# FMC_connector.net
KiCad netlist of a schematic drawn in Altium Designer
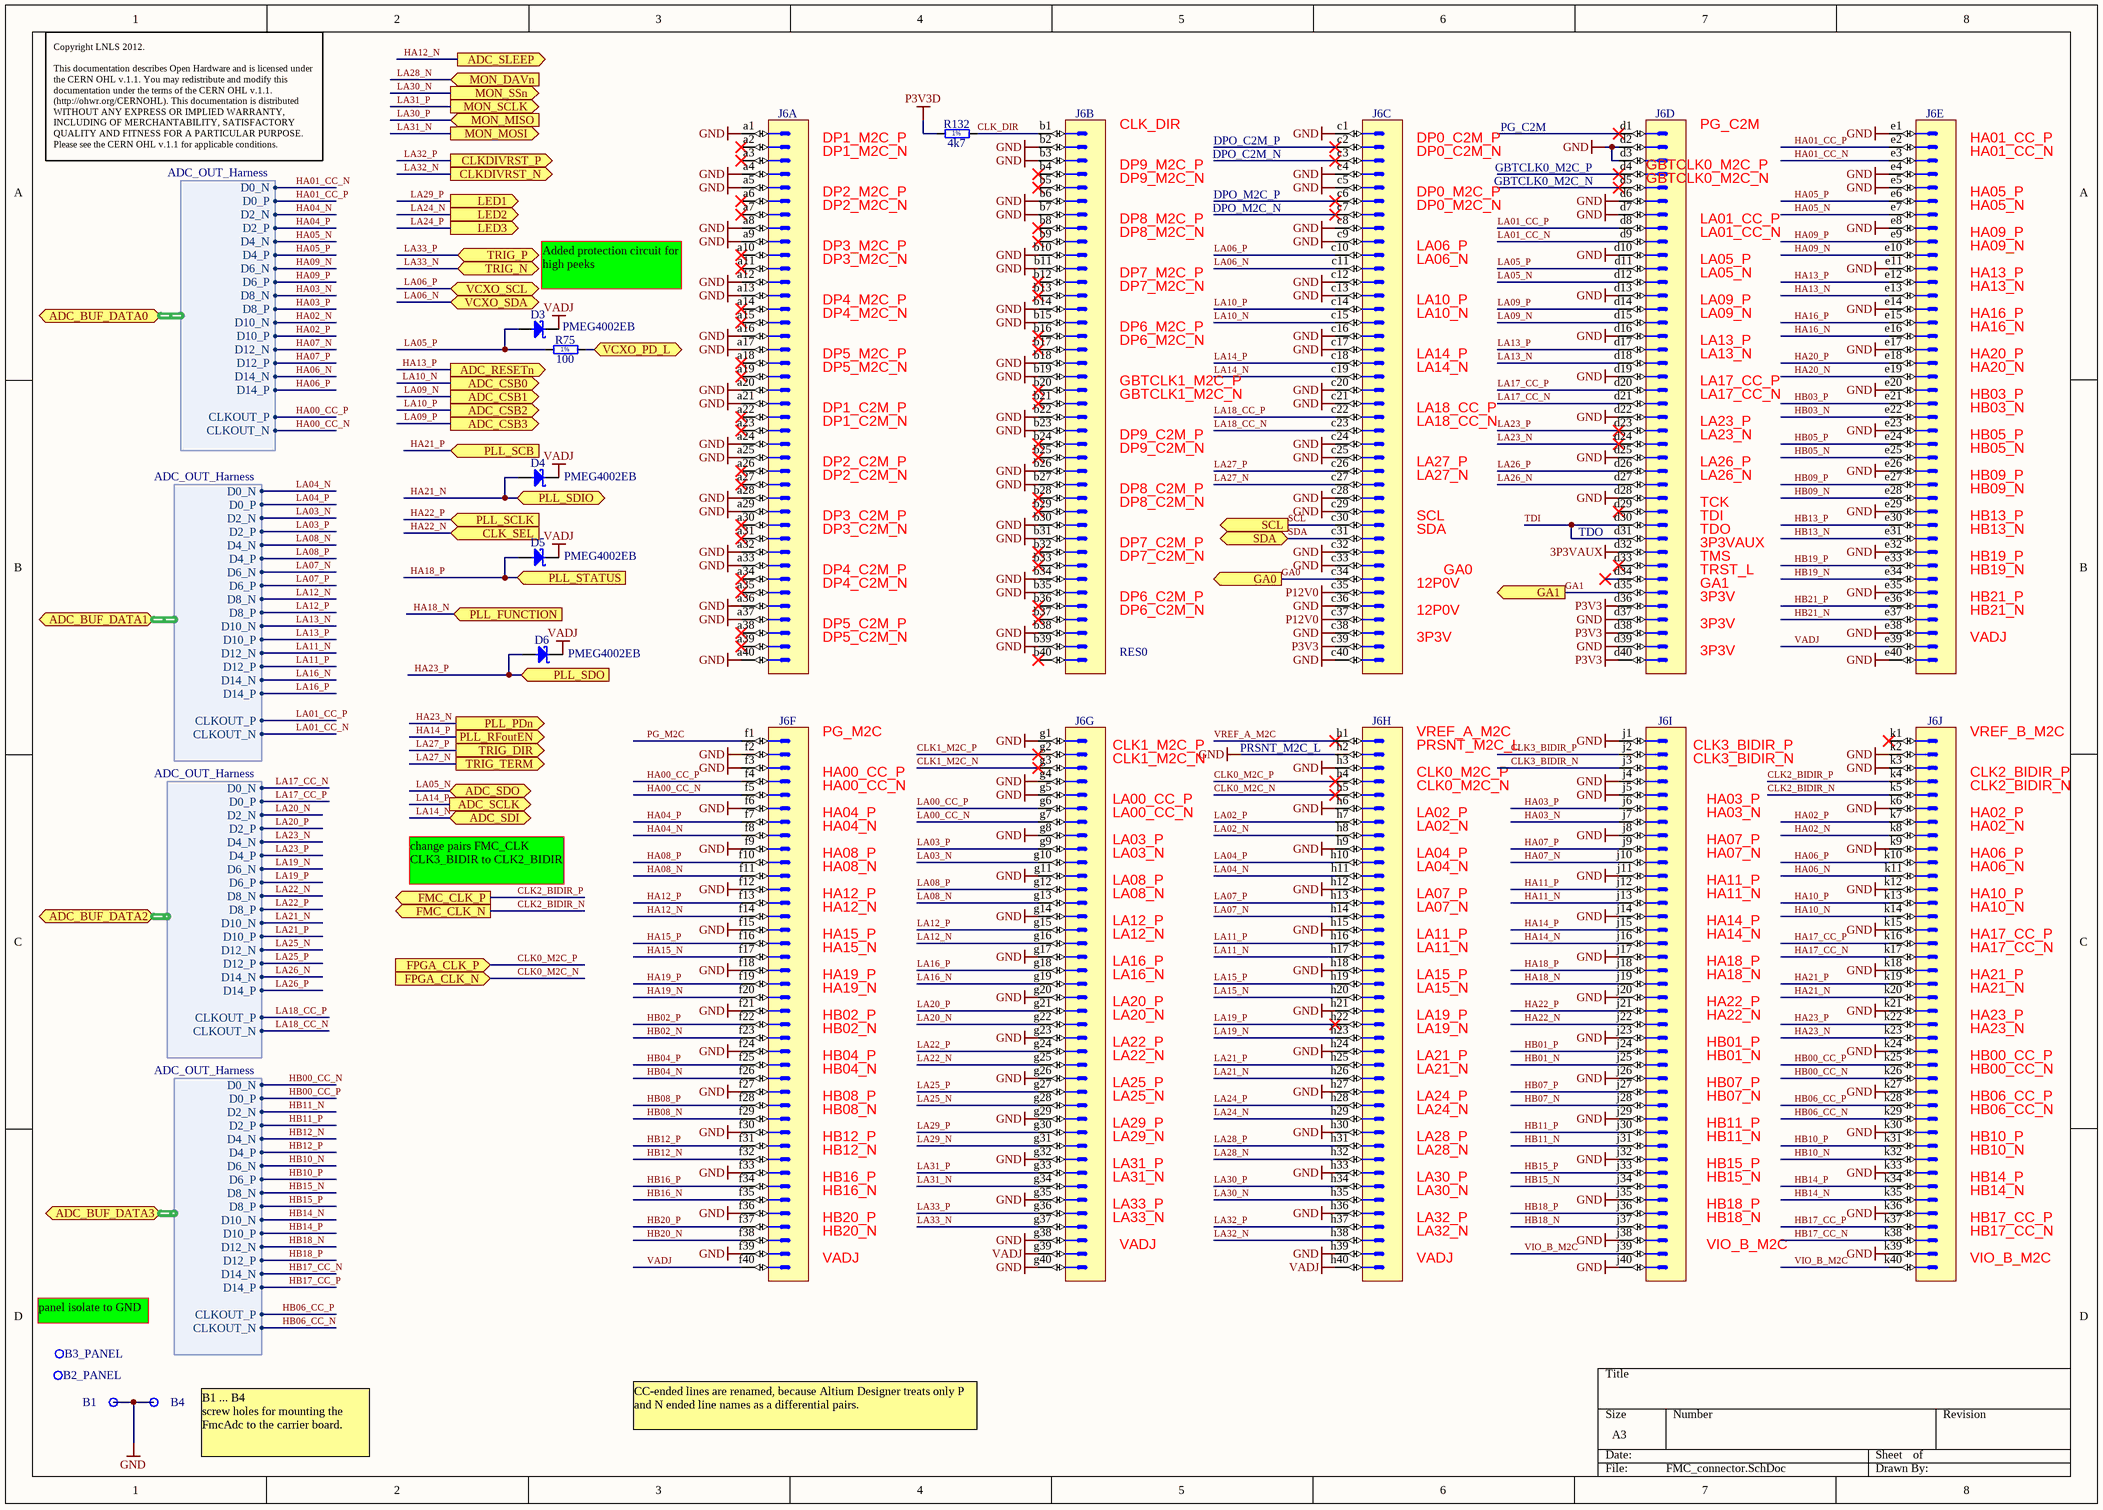
[diagram p0: FMC_connector.SchDoc]

(export (version "E")
  (design (tool "Eeschema 10.0.6"))
  (components
    (comp (ref "B1")
      (value "Plated Hole")
      (footprint "MTG270_500_M")
      (description "Single Terminal Socket")
      (fields (field (name "PART NUMBER") "PLATED_HOLE2.7_PAD5.0_M") (field (name "AUTHOR") "LNLS DIG FCS"))
      (libsource (lib "Eletro-mechanical") (part "Single Terminal Socket"))
    )
    (comp (ref "B2_PANEL")
      (value "Plated Hole")
      (footprint "MTG270_500_M")
      (description "Single Terminal Socket")
      (fields (field (name "PART NUMBER") "PLATED_HOLE2.7_PAD5.0_M") (field (name "AUTHOR") "LNLS DIG FCS"))
      (libsource (lib "Eletro-mechanical") (part "Single Terminal Socket"))
    )
    (comp (ref "B3_PANEL")
      (value "Plated Hole")
      (footprint "MTG270_500_M")
      (description "Single Terminal Socket")
      (fields (field (name "PART NUMBER") "PLATED_HOLE2.7_PAD5.0_M") (field (name "AUTHOR") "LNLS DIG FCS"))
      (libsource (lib "Eletro-mechanical") (part "Single Terminal Socket"))
    )
    (comp (ref "B4")
      (value "Plated Hole")
      (footprint "MTG270_500_M")
      (description "Single Terminal Socket")
      (fields (field (name "PART NUMBER") "PLATED_HOLE2.7_PAD5.0_M") (field (name "AUTHOR") "LNLS DIG FCS"))
      (libsource (lib "Eletro-mechanical") (part "Single Terminal Socket"))
    )
    (comp (ref "D3")
      (value "PMEG4002EB")
      (footprint "SODFL1608X65N")
      (description "Schottky Diode")
      (fields
        (field (name "VOLTAGE") "40V")
        (field (name "POWER") "200mA")
        (field (name "AUTHOR") "CERN DEM JMW")
      )
      (libsource (lib "ICs And Semiconductors") (part "Diode Schottky"))
    )
    (comp (ref "D4")
      (value "PMEG4002EB")
      (footprint "SODFL1608X65N")
      (description "Schottky Diode")
      (fields
        (field (name "VOLTAGE") "40V")
        (field (name "POWER") "200mA")
        (field (name "AUTHOR") "CERN DEM JMW")
      )
      (libsource (lib "ICs And Semiconductors") (part "Diode Schottky"))
    )
    (comp (ref "D5")
      (value "PMEG4002EB")
      (footprint "SODFL1608X65N")
      (description "Schottky Diode")
      (fields
        (field (name "VOLTAGE") "40V")
        (field (name "POWER") "200mA")
        (field (name "AUTHOR") "CERN DEM JMW")
      )
      (libsource (lib "ICs And Semiconductors") (part "Diode Schottky"))
    )
    (comp (ref "D6")
      (value "PMEG4002EB")
      (footprint "SODFL1608X65N")
      (description "Schottky Diode")
      (fields
        (field (name "VOLTAGE") "40V")
        (field (name "POWER") "200mA")
        (field (name "AUTHOR") "CERN DEM JMW")
      )
      (libsource (lib "ICs And Semiconductors") (part "Diode Schottky"))
    )
    (comp (ref "J6")
      (value "~")
      (footprint "SAMTEC_ASP-134488-01")
      (description "Connector VITA 57, 400 Male contacts in 10 row abcdefghj")
      (fields
        (field (name "PART NUMBER") "SAMTEC_ASP-134488-01")
        (field (name "MANUFACTURER") "SAMTEC")
        (field (name "AUTHOR") "CERN DEM JLC")
      )
      (libsource (lib "Connectors") (part "Connector VITA 57 400 Male (abcdefghjk)"))
    )
    (comp (ref "R75")
      (value "100")
      (footprint "RESC1005X40N")
      (description "Resistor - 1%")
      (fields
        (field (name "PART NUMBER") "R0402_100R_1%_0.0625W_100PPM")
        (field (name "POWER") "0.0625W")
        (field (name "AUTHOR") "CERN DEM JLC")
      )
      (libsource (lib "Resistors") (part "Resistor - 1%"))
    )
    (comp (ref "R132")
      (value "4k7")
      (footprint "RESC1005X40N")
      (description "Resistor - 1%")
      (fields
        (field (name "PART NUMBER") "R0402_4K7_1%_0.0625W_100PPM")
        (field (name "POWER") "0.0625W")
        (field (name "AUTHOR") "CERN DEM JLC")
      )
      (libsource (lib "Resistors") (part "Resistor - 1%"))
    )
  )
  (nets
    (net (code "2") (name "/CLK0_M2C_N") (class "Default")
      (node (ref "J6") (pin "h5") (pinfunction "h5_h5") (pintype "bidirectional+no_connect"))
    )
    (net (code "3") (name "/CLK0_M2C_P") (class "Default")
      (node (ref "J6") (pin "h4") (pinfunction "h4_h4") (pintype "bidirectional+no_connect"))
    )
    (net (code "4") (name "/CLK1_M2C_N") (class "Default")
      (node (ref "J6") (pin "g3") (pinfunction "g3_g3") (pintype "bidirectional+no_connect"))
    )
    (net (code "5") (name "/CLK1_M2C_P") (class "Default")
      (node (ref "J6") (pin "g2") (pinfunction "g2_g2") (pintype "bidirectional+no_connect"))
    )
    (net (code "6") (name "/CLK2_BIDIR_N") (class "Default")
      (node (ref "J6") (pin "k5") (pinfunction "k5_k5") (pintype "bidirectional"))
    )
    (net (code "7") (name "/CLK2_BIDIR_P") (class "Default")
      (node (ref "J6") (pin "k4") (pinfunction "k4_k4") (pintype "bidirectional"))
    )
    (net (code "8") (name "/CLK3_BIDIR_N") (class "Default")
      (node (ref "J6") (pin "j3") (pinfunction "j3_j3") (pintype "bidirectional"))
    )
    (net (code "9") (name "/CLK3_BIDIR_P") (class "Default")
      (node (ref "J6") (pin "j2") (pinfunction "j2_j2") (pintype "bidirectional"))
    )
    (net (code "10") (name "/CLK_DIR") (class "Default")
      (node (ref "J6") (pin "b1") (pinfunction "b1_b1") (pintype "bidirectional"))
      (node (ref "R132") (pin "2") (pinfunction "2_2") (pintype "passive"))
    )
    (net (code "11") (name "/GA0") (class "Default")
      (node (ref "J6") (pin "c34") (pinfunction "c34_c34") (pintype "bidirectional"))
    )
    (net (code "12") (name "/GA1") (class "Default")
      (node (ref "J6") (pin "d35") (pinfunction "d35_d35") (pintype "bidirectional"))
    )
    (net (code "13") (name "/HA00_CC_N") (class "Default")
      (node (ref "J6") (pin "f5") (pinfunction "f5_f5") (pintype "bidirectional"))
    )
    (net (code "14") (name "/HA00_CC_P") (class "Default")
      (node (ref "J6") (pin "f4") (pinfunction "f4_f4") (pintype "bidirectional"))
    )
    (net (code "15") (name "/HA01_CC_N") (class "Default")
      (node (ref "J6") (pin "e3") (pinfunction "e3_e3") (pintype "bidirectional"))
    )
    (net (code "16") (name "/HA01_CC_P") (class "Default")
      (node (ref "J6") (pin "e2") (pinfunction "e2_e2") (pintype "bidirectional"))
    )
    (net (code "17") (name "/HA02_N") (class "Default")
      (node (ref "J6") (pin "k8") (pinfunction "k8_k8") (pintype "bidirectional"))
    )
    (net (code "18") (name "/HA02_P") (class "Default")
      (node (ref "J6") (pin "k7") (pinfunction "k7_k7") (pintype "bidirectional"))
    )
    (net (code "19") (name "/HA03_N") (class "Default")
      (node (ref "J6") (pin "j7") (pinfunction "j7_j7") (pintype "bidirectional"))
    )
    (net (code "20") (name "/HA03_P") (class "Default")
      (node (ref "J6") (pin "j6") (pinfunction "j6_j6") (pintype "bidirectional"))
    )
    (net (code "21") (name "/HA04_N") (class "Default")
      (node (ref "J6") (pin "f8") (pinfunction "f8_f8") (pintype "bidirectional"))
    )
    (net (code "22") (name "/HA04_P") (class "Default")
      (node (ref "J6") (pin "f7") (pinfunction "f7_f7") (pintype "bidirectional"))
    )
    (net (code "23") (name "/HA05_N") (class "Default")
      (node (ref "J6") (pin "e7") (pinfunction "e7_e7") (pintype "bidirectional"))
    )
    (net (code "24") (name "/HA05_P") (class "Default")
      (node (ref "J6") (pin "e6") (pinfunction "e6_e6") (pintype "bidirectional"))
    )
    (net (code "25") (name "/HA06_N") (class "Default")
      (node (ref "J6") (pin "k11") (pinfunction "k11_k11") (pintype "bidirectional"))
    )
    (net (code "26") (name "/HA06_P") (class "Default")
      (node (ref "J6") (pin "k10") (pinfunction "k10_k10") (pintype "bidirectional"))
    )
    (net (code "27") (name "/HA07_N") (class "Default")
      (node (ref "J6") (pin "j10") (pinfunction "j10_j10") (pintype "bidirectional"))
    )
    (net (code "28") (name "/HA07_P") (class "Default")
      (node (ref "J6") (pin "j9") (pinfunction "j9_j9") (pintype "bidirectional"))
    )
    (net (code "29") (name "/HA08_N") (class "Default")
      (node (ref "J6") (pin "f11") (pinfunction "f11_f11") (pintype "bidirectional"))
    )
    (net (code "30") (name "/HA08_P") (class "Default")
      (node (ref "J6") (pin "f10") (pinfunction "f10_f10") (pintype "bidirectional"))
    )
    (net (code "31") (name "/HA09_N") (class "Default")
      (node (ref "J6") (pin "e10") (pinfunction "e10_e10") (pintype "bidirectional"))
    )
    (net (code "32") (name "/HA09_P") (class "Default")
      (node (ref "J6") (pin "e9") (pinfunction "e9_e9") (pintype "bidirectional"))
    )
    (net (code "33") (name "/HA10_N") (class "Default")
      (node (ref "J6") (pin "k14") (pinfunction "k14_k14") (pintype "bidirectional"))
    )
    (net (code "34") (name "/HA10_P") (class "Default")
      (node (ref "J6") (pin "k13") (pinfunction "k13_k13") (pintype "bidirectional"))
    )
    (net (code "35") (name "/HA11_N") (class "Default")
      (node (ref "J6") (pin "j13") (pinfunction "j13_j13") (pintype "bidirectional"))
    )
    (net (code "36") (name "/HA11_P") (class "Default")
      (node (ref "J6") (pin "j12") (pinfunction "j12_j12") (pintype "bidirectional"))
    )
    (net (code "37") (name "/HA12_N") (class "Default")
      (node (ref "J6") (pin "f14") (pinfunction "f14_f14") (pintype "bidirectional"))
    )
    (net (code "38") (name "/HA12_P") (class "Default")
      (node (ref "J6") (pin "f13") (pinfunction "f13_f13") (pintype "bidirectional"))
    )
    (net (code "39") (name "/HA13_N") (class "Default")
      (node (ref "J6") (pin "e13") (pinfunction "e13_e13") (pintype "bidirectional"))
    )
    (net (code "40") (name "/HA13_P") (class "Default")
      (node (ref "J6") (pin "e12") (pinfunction "e12_e12") (pintype "bidirectional"))
    )
    (net (code "41") (name "/HA14_N") (class "Default")
      (node (ref "J6") (pin "j16") (pinfunction "j16_j16") (pintype "bidirectional"))
    )
    (net (code "42") (name "/HA14_P") (class "Default")
      (node (ref "J6") (pin "j15") (pinfunction "j15_j15") (pintype "bidirectional"))
    )
    (net (code "43") (name "/HA15_N") (class "Default")
      (node (ref "J6") (pin "f17") (pinfunction "f17_f17") (pintype "bidirectional"))
    )
    (net (code "44") (name "/HA15_P") (class "Default")
      (node (ref "J6") (pin "f16") (pinfunction "f16_f16") (pintype "bidirectional"))
    )
    (net (code "45") (name "/HA16_N") (class "Default")
      (node (ref "J6") (pin "e16") (pinfunction "e16_e16") (pintype "bidirectional"))
    )
    (net (code "46") (name "/HA16_P") (class "Default")
      (node (ref "J6") (pin "e15") (pinfunction "e15_e15") (pintype "bidirectional"))
    )
    (net (code "47") (name "/HA17_CC_N") (class "Default")
      (node (ref "J6") (pin "k17") (pinfunction "k17_k17") (pintype "bidirectional"))
    )
    (net (code "48") (name "/HA17_CC_P") (class "Default")
      (node (ref "J6") (pin "k16") (pinfunction "k16_k16") (pintype "bidirectional"))
    )
    (net (code "49") (name "/HA18_N") (class "Default")
      (node (ref "J6") (pin "j19") (pinfunction "j19_j19") (pintype "bidirectional"))
    )
    (net (code "50") (name "/HA18_P") (class "Default")
      (node (ref "D5") (pin "2") (pinfunction "A_2") (pintype "passive"))
      (node (ref "J6") (pin "j18") (pinfunction "j18_j18") (pintype "bidirectional"))
    )
    (net (code "51") (name "/HA19_N") (class "Default")
      (node (ref "J6") (pin "f20") (pinfunction "f20_f20") (pintype "bidirectional"))
    )
    (net (code "52") (name "/HA19_P") (class "Default")
      (node (ref "J6") (pin "f19") (pinfunction "f19_f19") (pintype "bidirectional"))
    )
    (net (code "53") (name "/HA20_N") (class "Default")
      (node (ref "J6") (pin "e19") (pinfunction "e19_e19") (pintype "bidirectional"))
    )
    (net (code "54") (name "/HA20_P") (class "Default")
      (node (ref "J6") (pin "e18") (pinfunction "e18_e18") (pintype "bidirectional"))
    )
    (net (code "55") (name "/HA21_N") (class "Default")
      (node (ref "D4") (pin "2") (pinfunction "A_2") (pintype "passive"))
      (node (ref "J6") (pin "k20") (pinfunction "k20_k20") (pintype "bidirectional"))
    )
    (net (code "56") (name "/HA21_P") (class "Default")
      (node (ref "J6") (pin "k19") (pinfunction "k19_k19") (pintype "bidirectional"))
    )
    (net (code "57") (name "/HA22_N") (class "Default")
      (node (ref "J6") (pin "j22") (pinfunction "j22_j22") (pintype "bidirectional"))
    )
    (net (code "58") (name "/HA22_P") (class "Default")
      (node (ref "J6") (pin "j21") (pinfunction "j21_j21") (pintype "bidirectional"))
    )
    (net (code "59") (name "/HA23_N") (class "Default")
      (node (ref "J6") (pin "k23") (pinfunction "k23_k23") (pintype "bidirectional"))
    )
    (net (code "60") (name "/HA23_P") (class "Default")
      (node (ref "D6") (pin "2") (pinfunction "A_2") (pintype "passive"))
      (node (ref "J6") (pin "k22") (pinfunction "k22_k22") (pintype "bidirectional"))
    )
    (net (code "61") (name "/HB00_CC_N") (class "Default")
      (node (ref "J6") (pin "k26") (pinfunction "k26_k26") (pintype "bidirectional"))
    )
    (net (code "62") (name "/HB00_CC_P") (class "Default")
      (node (ref "J6") (pin "k25") (pinfunction "k25_k25") (pintype "bidirectional"))
    )
    (net (code "63") (name "/HB01_N") (class "Default")
      (node (ref "J6") (pin "j25") (pinfunction "j25_j25") (pintype "bidirectional"))
    )
    (net (code "64") (name "/HB01_P") (class "Default")
      (node (ref "J6") (pin "j24") (pinfunction "j24_j24") (pintype "bidirectional"))
    )
    (net (code "65") (name "/HB02_N") (class "Default")
      (node (ref "J6") (pin "f23") (pinfunction "f23_f23") (pintype "bidirectional"))
    )
    (net (code "66") (name "/HB02_P") (class "Default")
      (node (ref "J6") (pin "f22") (pinfunction "f22_f22") (pintype "bidirectional"))
    )
    (net (code "67") (name "/HB03_N") (class "Default")
      (node (ref "J6") (pin "e22") (pinfunction "e22_e22") (pintype "bidirectional"))
    )
    (net (code "68") (name "/HB03_P") (class "Default")
      (node (ref "J6") (pin "e21") (pinfunction "e21_e21") (pintype "bidirectional"))
    )
    (net (code "69") (name "/HB04_N") (class "Default")
      (node (ref "J6") (pin "f26") (pinfunction "f26_f26") (pintype "bidirectional"))
    )
    (net (code "70") (name "/HB04_P") (class "Default")
      (node (ref "J6") (pin "f25") (pinfunction "f25_f25") (pintype "bidirectional"))
    )
    (net (code "71") (name "/HB05_N") (class "Default")
      (node (ref "J6") (pin "e25") (pinfunction "e25_e25") (pintype "bidirectional"))
    )
    (net (code "72") (name "/HB05_P") (class "Default")
      (node (ref "J6") (pin "e24") (pinfunction "e24_e24") (pintype "bidirectional"))
    )
    (net (code "73") (name "/HB06_CC_N") (class "Default")
      (node (ref "J6") (pin "k29") (pinfunction "k29_k29") (pintype "bidirectional"))
    )
    (net (code "74") (name "/HB06_CC_P") (class "Default")
      (node (ref "J6") (pin "k28") (pinfunction "k28_k28") (pintype "bidirectional"))
    )
    (net (code "75") (name "/HB07_N") (class "Default")
      (node (ref "J6") (pin "j28") (pinfunction "j28_j28") (pintype "bidirectional"))
    )
    (net (code "76") (name "/HB07_P") (class "Default")
      (node (ref "J6") (pin "j27") (pinfunction "j27_j27") (pintype "bidirectional"))
    )
    (net (code "77") (name "/HB08_N") (class "Default")
      (node (ref "J6") (pin "f29") (pinfunction "f29_f29") (pintype "bidirectional"))
    )
    (net (code "78") (name "/HB08_P") (class "Default")
      (node (ref "J6") (pin "f28") (pinfunction "f28_f28") (pintype "bidirectional"))
    )
    (net (code "79") (name "/HB09_N") (class "Default")
      (node (ref "J6") (pin "e28") (pinfunction "e28_e28") (pintype "bidirectional"))
    )
    (net (code "80") (name "/HB09_P") (class "Default")
      (node (ref "J6") (pin "e27") (pinfunction "e27_e27") (pintype "bidirectional"))
    )
    (net (code "81") (name "/HB10_N") (class "Default")
      (node (ref "J6") (pin "k32") (pinfunction "k32_k32") (pintype "bidirectional"))
    )
    (net (code "82") (name "/HB10_P") (class "Default")
      (node (ref "J6") (pin "k31") (pinfunction "k31_k31") (pintype "bidirectional"))
    )
    (net (code "83") (name "/HB11_N") (class "Default")
      (node (ref "J6") (pin "j31") (pinfunction "j31_j31") (pintype "bidirectional"))
    )
    (net (code "84") (name "/HB11_P") (class "Default")
      (node (ref "J6") (pin "j30") (pinfunction "j30_j30") (pintype "bidirectional"))
    )
    (net (code "85") (name "/HB12_N") (class "Default")
      (node (ref "J6") (pin "f32") (pinfunction "f32_f32") (pintype "bidirectional"))
    )
    (net (code "86") (name "/HB12_P") (class "Default")
      (node (ref "J6") (pin "f31") (pinfunction "f31_f31") (pintype "bidirectional"))
    )
    (net (code "87") (name "/HB13_N") (class "Default")
      (node (ref "J6") (pin "e31") (pinfunction "e31_e31") (pintype "bidirectional"))
    )
    (net (code "88") (name "/HB13_P") (class "Default")
      (node (ref "J6") (pin "e30") (pinfunction "e30_e30") (pintype "bidirectional"))
    )
    (net (code "89") (name "/HB14_N") (class "Default")
      (node (ref "J6") (pin "k35") (pinfunction "k35_k35") (pintype "bidirectional"))
    )
    (net (code "90") (name "/HB14_P") (class "Default")
      (node (ref "J6") (pin "k34") (pinfunction "k34_k34") (pintype "bidirectional"))
    )
    (net (code "91") (name "/HB15_N") (class "Default")
      (node (ref "J6") (pin "j34") (pinfunction "j34_j34") (pintype "bidirectional"))
    )
    (net (code "92") (name "/HB15_P") (class "Default")
      (node (ref "J6") (pin "j33") (pinfunction "j33_j33") (pintype "bidirectional"))
    )
    (net (code "93") (name "/HB16_N") (class "Default")
      (node (ref "J6") (pin "f35") (pinfunction "f35_f35") (pintype "bidirectional"))
    )
    (net (code "94") (name "/HB16_P") (class "Default")
      (node (ref "J6") (pin "f34") (pinfunction "f34_f34") (pintype "bidirectional"))
    )
    (net (code "95") (name "/HB17_CC_N") (class "Default")
      (node (ref "J6") (pin "k38") (pinfunction "k38_k38") (pintype "bidirectional"))
    )
    (net (code "96") (name "/HB17_CC_P") (class "Default")
      (node (ref "J6") (pin "k37") (pinfunction "k37_k37") (pintype "bidirectional"))
    )
    (net (code "97") (name "/HB18_N") (class "Default")
      (node (ref "J6") (pin "j37") (pinfunction "j37_j37") (pintype "bidirectional"))
    )
    (net (code "98") (name "/HB18_P") (class "Default")
      (node (ref "J6") (pin "j36") (pinfunction "j36_j36") (pintype "bidirectional"))
    )
    (net (code "99") (name "/HB19_N") (class "Default")
      (node (ref "J6") (pin "e34") (pinfunction "e34_e34") (pintype "bidirectional"))
    )
    (net (code "100") (name "/HB19_P") (class "Default")
      (node (ref "J6") (pin "e33") (pinfunction "e33_e33") (pintype "bidirectional"))
    )
    (net (code "101") (name "/HB20_N") (class "Default")
      (node (ref "J6") (pin "f38") (pinfunction "f38_f38") (pintype "bidirectional"))
    )
    (net (code "102") (name "/HB20_P") (class "Default")
      (node (ref "J6") (pin "f37") (pinfunction "f37_f37") (pintype "bidirectional"))
    )
    (net (code "103") (name "/HB21_N") (class "Default")
      (node (ref "J6") (pin "e37") (pinfunction "e37_e37") (pintype "bidirectional"))
    )
    (net (code "104") (name "/HB21_P") (class "Default")
      (node (ref "J6") (pin "e36") (pinfunction "e36_e36") (pintype "bidirectional"))
    )
    (net (code "105") (name "/LA00_CC_N") (class "Default")
      (node (ref "J6") (pin "g7") (pinfunction "g7_g7") (pintype "bidirectional"))
    )
    (net (code "106") (name "/LA00_CC_P") (class "Default")
      (node (ref "J6") (pin "g6") (pinfunction "g6_g6") (pintype "bidirectional"))
    )
    (net (code "107") (name "/LA01_CC_N") (class "Default")
      (node (ref "J6") (pin "d9") (pinfunction "d9_d9") (pintype "bidirectional"))
    )
    (net (code "108") (name "/LA01_CC_P") (class "Default")
      (node (ref "J6") (pin "d8") (pinfunction "d8_d8") (pintype "bidirectional"))
    )
    (net (code "109") (name "/LA02_N") (class "Default")
      (node (ref "J6") (pin "h8") (pinfunction "h8_h8") (pintype "bidirectional"))
    )
    (net (code "110") (name "/LA02_P") (class "Default")
      (node (ref "J6") (pin "h7") (pinfunction "h7_h7") (pintype "bidirectional"))
    )
    (net (code "111") (name "/LA03_N") (class "Default")
      (node (ref "J6") (pin "g10") (pinfunction "g10_g10") (pintype "bidirectional"))
    )
    (net (code "112") (name "/LA03_P") (class "Default")
      (node (ref "J6") (pin "g9") (pinfunction "g9_g9") (pintype "bidirectional"))
    )
    (net (code "113") (name "/LA04_N") (class "Default")
      (node (ref "J6") (pin "h11") (pinfunction "h11_h11") (pintype "bidirectional"))
    )
    (net (code "114") (name "/LA04_P") (class "Default")
      (node (ref "J6") (pin "h10") (pinfunction "h10_h10") (pintype "bidirectional"))
    )
    (net (code "115") (name "/LA05_N") (class "Default")
      (node (ref "J6") (pin "d12") (pinfunction "d12_d12") (pintype "bidirectional"))
    )
    (net (code "116") (name "/LA05_P") (class "Default")
      (node (ref "D3") (pin "2") (pinfunction "A_2") (pintype "passive"))
      (node (ref "J6") (pin "d11") (pinfunction "d11_d11") (pintype "bidirectional"))
      (node (ref "R75") (pin "1") (pinfunction "1_1") (pintype "passive"))
    )
    (net (code "117") (name "/LA06_N") (class "Default")
      (node (ref "J6") (pin "c11") (pinfunction "c11_c11") (pintype "bidirectional"))
    )
    (net (code "118") (name "/LA06_P") (class "Default")
      (node (ref "J6") (pin "c10") (pinfunction "c10_c10") (pintype "bidirectional"))
    )
    (net (code "119") (name "/LA07_N") (class "Default")
      (node (ref "J6") (pin "h14") (pinfunction "h14_h14") (pintype "bidirectional"))
    )
    (net (code "120") (name "/LA07_P") (class "Default")
      (node (ref "J6") (pin "h13") (pinfunction "h13_h13") (pintype "bidirectional"))
    )
    (net (code "121") (name "/LA08_N") (class "Default")
      (node (ref "J6") (pin "g13") (pinfunction "g13_g13") (pintype "bidirectional"))
    )
    (net (code "122") (name "/LA08_P") (class "Default")
      (node (ref "J6") (pin "g12") (pinfunction "g12_g12") (pintype "bidirectional"))
    )
    (net (code "123") (name "/LA09_N") (class "Default")
      (node (ref "J6") (pin "d15") (pinfunction "d15_d15") (pintype "bidirectional"))
    )
    (net (code "124") (name "/LA09_P") (class "Default")
      (node (ref "J6") (pin "d14") (pinfunction "d14_d14") (pintype "bidirectional"))
    )
    (net (code "125") (name "/LA10_N") (class "Default")
      (node (ref "J6") (pin "c15") (pinfunction "c15_c15") (pintype "bidirectional"))
    )
    (net (code "126") (name "/LA10_P") (class "Default")
      (node (ref "J6") (pin "c14") (pinfunction "c14_c14") (pintype "bidirectional"))
    )
    (net (code "127") (name "/LA11_N") (class "Default")
      (node (ref "J6") (pin "h17") (pinfunction "h17_h17") (pintype "bidirectional"))
    )
    (net (code "128") (name "/LA11_P") (class "Default")
      (node (ref "J6") (pin "h16") (pinfunction "h16_h16") (pintype "bidirectional"))
    )
    (net (code "129") (name "/LA12_N") (class "Default")
      (node (ref "J6") (pin "g16") (pinfunction "g16_g16") (pintype "bidirectional"))
    )
    (net (code "130") (name "/LA12_P") (class "Default")
      (node (ref "J6") (pin "g15") (pinfunction "g15_g15") (pintype "bidirectional"))
    )
    (net (code "131") (name "/LA13_N") (class "Default")
      (node (ref "J6") (pin "d18") (pinfunction "d18_d18") (pintype "bidirectional"))
    )
    (net (code "132") (name "/LA13_P") (class "Default")
      (node (ref "J6") (pin "d17") (pinfunction "d17_d17") (pintype "bidirectional"))
    )
    (net (code "133") (name "/LA14_N") (class "Default")
      (node (ref "J6") (pin "c19") (pinfunction "c19_c19") (pintype "bidirectional"))
    )
    (net (code "134") (name "/LA14_P") (class "Default")
      (node (ref "J6") (pin "c18") (pinfunction "c18_c18") (pintype "bidirectional"))
    )
    (net (code "135") (name "/LA15_N") (class "Default")
      (node (ref "J6") (pin "h20") (pinfunction "h20_h20") (pintype "bidirectional"))
    )
    (net (code "136") (name "/LA15_P") (class "Default")
      (node (ref "J6") (pin "h19") (pinfunction "h19_h19") (pintype "bidirectional"))
    )
    (net (code "137") (name "/LA16_N") (class "Default")
      (node (ref "J6") (pin "g19") (pinfunction "g19_g19") (pintype "bidirectional"))
    )
    (net (code "138") (name "/LA16_P") (class "Default")
      (node (ref "J6") (pin "g18") (pinfunction "g18_g18") (pintype "bidirectional"))
    )
    (net (code "139") (name "/LA17_CC_N") (class "Default")
      (node (ref "J6") (pin "d21") (pinfunction "d21_d21") (pintype "bidirectional"))
    )
    (net (code "140") (name "/LA17_CC_P") (class "Default")
      (node (ref "J6") (pin "d20") (pinfunction "d20_d20") (pintype "bidirectional"))
    )
    (net (code "141") (name "/LA18_CC_N") (class "Default")
      (node (ref "J6") (pin "c23") (pinfunction "c23_c23") (pintype "bidirectional"))
    )
    (net (code "142") (name "/LA18_CC_P") (class "Default")
      (node (ref "J6") (pin "c22") (pinfunction "c22_c22") (pintype "bidirectional"))
    )
    (net (code "143") (name "/LA19_N") (class "Default")
      (node (ref "J6") (pin "h23") (pinfunction "h23_h23") (pintype "bidirectional"))
    )
    (net (code "144") (name "/LA19_P") (class "Default")
      (node (ref "J6") (pin "h22") (pinfunction "h22_h22") (pintype "bidirectional+no_connect"))
    )
    (net (code "145") (name "/LA20_N") (class "Default")
      (node (ref "J6") (pin "g22") (pinfunction "g22_g22") (pintype "bidirectional"))
    )
    (net (code "146") (name "/LA20_P") (class "Default")
      (node (ref "J6") (pin "g21") (pinfunction "g21_g21") (pintype "bidirectional"))
    )
    (net (code "147") (name "/LA21_N") (class "Default")
      (node (ref "J6") (pin "h26") (pinfunction "h26_h26") (pintype "bidirectional"))
    )
    (net (code "148") (name "/LA21_P") (class "Default")
      (node (ref "J6") (pin "h25") (pinfunction "h25_h25") (pintype "bidirectional"))
    )
    (net (code "149") (name "/LA22_N") (class "Default")
      (node (ref "J6") (pin "g25") (pinfunction "g25_g25") (pintype "bidirectional"))
    )
    (net (code "150") (name "/LA22_P") (class "Default")
      (node (ref "J6") (pin "g24") (pinfunction "g24_g24") (pintype "bidirectional"))
    )
    (net (code "151") (name "/LA23_N") (class "Default")
      (node (ref "J6") (pin "d24") (pinfunction "d24_d24") (pintype "bidirectional"))
    )
    (net (code "152") (name "/LA23_P") (class "Default")
      (node (ref "J6") (pin "d23") (pinfunction "d23_d23") (pintype "bidirectional"))
    )
    (net (code "153") (name "/LA24_N") (class "Default")
      (node (ref "J6") (pin "h29") (pinfunction "h29_h29") (pintype "bidirectional"))
    )
    (net (code "154") (name "/LA24_P") (class "Default")
      (node (ref "J6") (pin "h28") (pinfunction "h28_h28") (pintype "bidirectional"))
    )
    (net (code "155") (name "/LA25_N") (class "Default")
      (node (ref "J6") (pin "g28") (pinfunction "g28_g28") (pintype "bidirectional"))
    )
    (net (code "156") (name "/LA25_P") (class "Default")
      (node (ref "J6") (pin "g27") (pinfunction "g27_g27") (pintype "bidirectional"))
    )
    (net (code "157") (name "/LA26_N") (class "Default")
      (node (ref "J6") (pin "d27") (pinfunction "d27_d27") (pintype "bidirectional"))
    )
    (net (code "158") (name "/LA26_P") (class "Default")
      (node (ref "J6") (pin "d26") (pinfunction "d26_d26") (pintype "bidirectional"))
    )
    (net (code "159") (name "/LA27_N") (class "Default")
      (node (ref "J6") (pin "c27") (pinfunction "c27_c27") (pintype "bidirectional"))
    )
    (net (code "160") (name "/LA27_P") (class "Default")
      (node (ref "J6") (pin "c26") (pinfunction "c26_c26") (pintype "bidirectional"))
    )
    (net (code "161") (name "/LA28_N") (class "Default")
      (node (ref "J6") (pin "h32") (pinfunction "h32_h32") (pintype "bidirectional"))
    )
    (net (code "162") (name "/LA28_P") (class "Default")
      (node (ref "J6") (pin "h31") (pinfunction "h31_h31") (pintype "bidirectional"))
    )
    (net (code "163") (name "/LA29_N") (class "Default")
      (node (ref "J6") (pin "g31") (pinfunction "g31_g31") (pintype "bidirectional"))
    )
    (net (code "164") (name "/LA29_P") (class "Default")
      (node (ref "J6") (pin "g30") (pinfunction "g30_g30") (pintype "bidirectional"))
    )
    (net (code "165") (name "/LA30_N") (class "Default")
      (node (ref "J6") (pin "h35") (pinfunction "h35_h35") (pintype "bidirectional"))
    )
    (net (code "166") (name "/LA30_P") (class "Default")
      (node (ref "J6") (pin "h34") (pinfunction "h34_h34") (pintype "bidirectional"))
    )
    (net (code "167") (name "/LA31_N") (class "Default")
      (node (ref "J6") (pin "g34") (pinfunction "g34_g34") (pintype "bidirectional"))
    )
    (net (code "168") (name "/LA31_P") (class "Default")
      (node (ref "J6") (pin "g33") (pinfunction "g33_g33") (pintype "bidirectional"))
    )
    (net (code "169") (name "/LA32_N") (class "Default")
      (node (ref "J6") (pin "h38") (pinfunction "h38_h38") (pintype "bidirectional"))
    )
    (net (code "170") (name "/LA32_P") (class "Default")
      (node (ref "J6") (pin "h37") (pinfunction "h37_h37") (pintype "bidirectional"))
    )
    (net (code "171") (name "/LA33_N") (class "Default")
      (node (ref "J6") (pin "g37") (pinfunction "g37_g37") (pintype "bidirectional"))
    )
    (net (code "172") (name "/LA33_P") (class "Default")
      (node (ref "J6") (pin "g36") (pinfunction "g36_g36") (pintype "bidirectional"))
    )
    (net (code "173") (name "/PG_M2C") (class "Default")
      (node (ref "J6") (pin "f1") (pinfunction "f1_f1") (pintype "bidirectional"))
    )
    (net (code "174") (name "/SCL") (class "Default")
      (node (ref "J6") (pin "c30") (pinfunction "c30_c30") (pintype "bidirectional"))
    )
    (net (code "175") (name "/SDA") (class "Default")
      (node (ref "J6") (pin "c31") (pinfunction "c31_c31") (pintype "bidirectional"))
    )
    (net (code "176") (name "/TDI") (class "Default")
      (node (ref "J6") (pin "d30") (pinfunction "d30_d30") (pintype "bidirectional"))
      (node (ref "J6") (pin "d31") (pinfunction "d31_d31") (pintype "bidirectional"))
    )
    (net (code "177") (name "/VCXO_PD_L") (class "Default")
      (node (ref "R75") (pin "2") (pinfunction "2_2") (pintype "passive"))
    )
    (net (code "178") (name "/VIO_B_M2C") (class "Default")
      (node (ref "J6") (pin "j39") (pinfunction "j39_j39") (pintype "bidirectional"))
      (node (ref "J6") (pin "k40") (pinfunction "k40_k40") (pintype "bidirectional"))
    )
    (net (code "179") (name "/VREF_A_M2C") (class "Default")
      (node (ref "J6") (pin "h1") (pinfunction "h1_h1") (pintype "bidirectional+no_connect"))
    )
    (net (code "181") (name "3P3VAUX") (class "Default")
      (node (ref "J6") (pin "d32") (pinfunction "d32_d32") (pintype "bidirectional"))
    )
    (net (code "182") (name "GND") (class "Default")
      (node (ref "B1") (pin "1") (pinfunction "1_1") (pintype "bidirectional"))
      (node (ref "B4") (pin "1") (pinfunction "1_1") (pintype "bidirectional"))
      (node (ref "J6") (pin "a1") (pinfunction "a1_a1") (pintype "bidirectional"))
      (node (ref "J6") (pin "a12") (pinfunction "a12_a12") (pintype "bidirectional"))
      (node (ref "J6") (pin "a13") (pinfunction "a13_a13") (pintype "bidirectional"))
      (node (ref "J6") (pin "a16") (pinfunction "a16_a16") (pintype "bidirectional"))
      (node (ref "J6") (pin "a17") (pinfunction "a17_a17") (pintype "bidirectional"))
      (node (ref "J6") (pin "a20") (pinfunction "a20_a20") (pintype "bidirectional"))
      (node (ref "J6") (pin "a21") (pinfunction "a21_a21") (pintype "bidirectional"))
      (node (ref "J6") (pin "a24") (pinfunction "a24_a24") (pintype "bidirectional"))
      (node (ref "J6") (pin "a25") (pinfunction "a25_a25") (pintype "bidirectional"))
      (node (ref "J6") (pin "a28") (pinfunction "a28_a28") (pintype "bidirectional"))
      (node (ref "J6") (pin "a29") (pinfunction "a29_a29") (pintype "bidirectional"))
      (node (ref "J6") (pin "a32") (pinfunction "a32_a32") (pintype "bidirectional"))
      (node (ref "J6") (pin "a33") (pinfunction "a33_a33") (pintype "bidirectional"))
      (node (ref "J6") (pin "a36") (pinfunction "a36_a36") (pintype "bidirectional"))
      (node (ref "J6") (pin "a37") (pinfunction "a37_a37") (pintype "bidirectional"))
      (node (ref "J6") (pin "a4") (pinfunction "a4_a4") (pintype "bidirectional"))
      (node (ref "J6") (pin "a40") (pinfunction "a40_a40") (pintype "bidirectional"))
      (node (ref "J6") (pin "a5") (pinfunction "a5_a5") (pintype "bidirectional"))
      (node (ref "J6") (pin "a8") (pinfunction "a8_a8") (pintype "bidirectional"))
      (node (ref "J6") (pin "a9") (pinfunction "a9_a9") (pintype "bidirectional"))
      (node (ref "J6") (pin "b10") (pinfunction "b10_b10") (pintype "bidirectional"))
      (node (ref "J6") (pin "b11") (pinfunction "b11_b11") (pintype "bidirectional"))
      (node (ref "J6") (pin "b14") (pinfunction "b14_b14") (pintype "bidirectional"))
      (node (ref "J6") (pin "b15") (pinfunction "b15_b15") (pintype "bidirectional"))
      (node (ref "J6") (pin "b18") (pinfunction "b18_b18") (pintype "bidirectional"))
      (node (ref "J6") (pin "b19") (pinfunction "b19_b19") (pintype "bidirectional"))
      (node (ref "J6") (pin "b2") (pinfunction "b2_b2") (pintype "bidirectional"))
      (node (ref "J6") (pin "b22") (pinfunction "b22_b22") (pintype "bidirectional"))
      (node (ref "J6") (pin "b23") (pinfunction "b23_b23") (pintype "bidirectional"))
      (node (ref "J6") (pin "b26") (pinfunction "b26_b26") (pintype "bidirectional"))
      (node (ref "J6") (pin "b27") (pinfunction "b27_b27") (pintype "bidirectional"))
      (node (ref "J6") (pin "b3") (pinfunction "b3_b3") (pintype "bidirectional"))
      (node (ref "J6") (pin "b30") (pinfunction "b30_b30") (pintype "bidirectional"))
      (node (ref "J6") (pin "b31") (pinfunction "b31_b31") (pintype "bidirectional"))
      (node (ref "J6") (pin "b34") (pinfunction "b34_b34") (pintype "bidirectional"))
      (node (ref "J6") (pin "b35") (pinfunction "b35_b35") (pintype "bidirectional"))
      (node (ref "J6") (pin "b38") (pinfunction "b38_b38") (pintype "bidirectional"))
      (node (ref "J6") (pin "b39") (pinfunction "b39_b39") (pintype "bidirectional"))
      (node (ref "J6") (pin "b6") (pinfunction "b6_b6") (pintype "bidirectional"))
      (node (ref "J6") (pin "b7") (pinfunction "b7_b7") (pintype "bidirectional"))
      (node (ref "J6") (pin "c1") (pinfunction "c1_c1") (pintype "bidirectional"))
      (node (ref "J6") (pin "c12") (pinfunction "c12_c12") (pintype "bidirectional"))
      (node (ref "J6") (pin "c13") (pinfunction "c13_c13") (pintype "bidirectional"))
      (node (ref "J6") (pin "c16") (pinfunction "c16_c16") (pintype "bidirectional"))
      (node (ref "J6") (pin "c17") (pinfunction "c17_c17") (pintype "bidirectional"))
      (node (ref "J6") (pin "c20") (pinfunction "c20_c20") (pintype "bidirectional"))
      (node (ref "J6") (pin "c21") (pinfunction "c21_c21") (pintype "bidirectional"))
      (node (ref "J6") (pin "c24") (pinfunction "c24_c24") (pintype "bidirectional"))
      (node (ref "J6") (pin "c25") (pinfunction "c25_c25") (pintype "bidirectional"))
      (node (ref "J6") (pin "c28") (pinfunction "c28_c28") (pintype "bidirectional"))
      (node (ref "J6") (pin "c29") (pinfunction "c29_c29") (pintype "bidirectional"))
      (node (ref "J6") (pin "c32") (pinfunction "c32_c32") (pintype "bidirectional"))
      (node (ref "J6") (pin "c33") (pinfunction "c33_c33") (pintype "bidirectional"))
      (node (ref "J6") (pin "c36") (pinfunction "c36_c36") (pintype "bidirectional"))
      (node (ref "J6") (pin "c38") (pinfunction "c38_c38") (pintype "bidirectional"))
      (node (ref "J6") (pin "c4") (pinfunction "c4_c4") (pintype "bidirectional"))
      (node (ref "J6") (pin "c40") (pinfunction "c40_c40") (pintype "bidirectional"))
      (node (ref "J6") (pin "c5") (pinfunction "c5_c5") (pintype "bidirectional"))
      (node (ref "J6") (pin "c8") (pinfunction "c8_c8") (pintype "bidirectional"))
      (node (ref "J6") (pin "c9") (pinfunction "c9_c9") (pintype "bidirectional"))
      (node (ref "J6") (pin "d10") (pinfunction "d10_d10") (pintype "bidirectional"))
      (node (ref "J6") (pin "d13") (pinfunction "d13_d13") (pintype "bidirectional"))
      (node (ref "J6") (pin "d16") (pinfunction "d16_d16") (pintype "bidirectional"))
      (node (ref "J6") (pin "d19") (pinfunction "d19_d19") (pintype "bidirectional"))
      (node (ref "J6") (pin "d2") (pinfunction "d2_d2") (pintype "bidirectional"))
      (node (ref "J6") (pin "d22") (pinfunction "d22_d22") (pintype "bidirectional"))
      (node (ref "J6") (pin "d25") (pinfunction "d25_d25") (pintype "bidirectional"))
      (node (ref "J6") (pin "d28") (pinfunction "d28_d28") (pintype "bidirectional"))
      (node (ref "J6") (pin "d3") (pinfunction "d3_d3") (pintype "bidirectional"))
      (node (ref "J6") (pin "d37") (pinfunction "d37_d37") (pintype "bidirectional"))
      (node (ref "J6") (pin "d39") (pinfunction "d39_d39") (pintype "bidirectional"))
      (node (ref "J6") (pin "d6") (pinfunction "d6_d6") (pintype "bidirectional"))
      (node (ref "J6") (pin "d7") (pinfunction "d7_d7") (pintype "bidirectional"))
      (node (ref "J6") (pin "e1") (pinfunction "e1_e1") (pintype "bidirectional"))
      (node (ref "J6") (pin "e11") (pinfunction "e11_e11") (pintype "bidirectional"))
      (node (ref "J6") (pin "e14") (pinfunction "e14_e14") (pintype "bidirectional"))
      (node (ref "J6") (pin "e17") (pinfunction "e17_e17") (pintype "bidirectional"))
      (node (ref "J6") (pin "e20") (pinfunction "e20_e20") (pintype "bidirectional"))
      (node (ref "J6") (pin "e23") (pinfunction "e23_e23") (pintype "bidirectional"))
      (node (ref "J6") (pin "e26") (pinfunction "e26_e26") (pintype "bidirectional"))
      (node (ref "J6") (pin "e29") (pinfunction "e29_e29") (pintype "bidirectional"))
      (node (ref "J6") (pin "e32") (pinfunction "e32_e32") (pintype "bidirectional"))
      (node (ref "J6") (pin "e35") (pinfunction "e35_e35") (pintype "bidirectional"))
      (node (ref "J6") (pin "e38") (pinfunction "e38_e38") (pintype "bidirectional"))
      (node (ref "J6") (pin "e4") (pinfunction "e4_e4") (pintype "bidirectional"))
      (node (ref "J6") (pin "e40") (pinfunction "e40_e40") (pintype "bidirectional"))
      (node (ref "J6") (pin "e5") (pinfunction "e5_e5") (pintype "bidirectional"))
      (node (ref "J6") (pin "e8") (pinfunction "e8_e8") (pintype "bidirectional"))
      (node (ref "J6") (pin "f12") (pinfunction "f12_f12") (pintype "bidirectional"))
      (node (ref "J6") (pin "f15") (pinfunction "f15_f15") (pintype "bidirectional"))
      (node (ref "J6") (pin "f18") (pinfunction "f18_f18") (pintype "bidirectional"))
      (node (ref "J6") (pin "f2") (pinfunction "f2_f2") (pintype "bidirectional"))
      (node (ref "J6") (pin "f21") (pinfunction "f21_f21") (pintype "bidirectional"))
      (node (ref "J6") (pin "f24") (pinfunction "f24_f24") (pintype "bidirectional"))
      (node (ref "J6") (pin "f27") (pinfunction "f27_f27") (pintype "bidirectional"))
      (node (ref "J6") (pin "f3") (pinfunction "f3_f3") (pintype "bidirectional"))
      (node (ref "J6") (pin "f30") (pinfunction "f30_f30") (pintype "bidirectional"))
      (node (ref "J6") (pin "f33") (pinfunction "f33_f33") (pintype "bidirectional"))
      (node (ref "J6") (pin "f36") (pinfunction "f36_f36") (pintype "bidirectional"))
      (node (ref "J6") (pin "f39") (pinfunction "f39_f39") (pintype "bidirectional"))
      (node (ref "J6") (pin "f6") (pinfunction "f6_f6") (pintype "bidirectional"))
      (node (ref "J6") (pin "f9") (pinfunction "f9_f9") (pintype "bidirectional"))
      (node (ref "J6") (pin "g1") (pinfunction "g1_g1") (pintype "bidirectional"))
      (node (ref "J6") (pin "g11") (pinfunction "g11_g11") (pintype "bidirectional"))
      (node (ref "J6") (pin "g14") (pinfunction "g14_g14") (pintype "bidirectional"))
      (node (ref "J6") (pin "g17") (pinfunction "g17_g17") (pintype "bidirectional"))
      (node (ref "J6") (pin "g20") (pinfunction "g20_g20") (pintype "bidirectional"))
      (node (ref "J6") (pin "g23") (pinfunction "g23_g23") (pintype "bidirectional"))
      (node (ref "J6") (pin "g26") (pinfunction "g26_g26") (pintype "bidirectional"))
      (node (ref "J6") (pin "g29") (pinfunction "g29_g29") (pintype "bidirectional"))
      (node (ref "J6") (pin "g32") (pinfunction "g32_g32") (pintype "bidirectional"))
      (node (ref "J6") (pin "g35") (pinfunction "g35_g35") (pintype "bidirectional"))
      (node (ref "J6") (pin "g38") (pinfunction "g38_g38") (pintype "bidirectional"))
      (node (ref "J6") (pin "g4") (pinfunction "g4_g4") (pintype "bidirectional"))
      (node (ref "J6") (pin "g40") (pinfunction "g40_g40") (pintype "bidirectional"))
      (node (ref "J6") (pin "g5") (pinfunction "g5_g5") (pintype "bidirectional"))
      (node (ref "J6") (pin "g8") (pinfunction "g8_g8") (pintype "bidirectional"))
      (node (ref "J6") (pin "h12") (pinfunction "h12_h12") (pintype "bidirectional"))
      (node (ref "J6") (pin "h15") (pinfunction "h15_h15") (pintype "bidirectional"))
      (node (ref "J6") (pin "h18") (pinfunction "h18_h18") (pintype "bidirectional"))
      (node (ref "J6") (pin "h2") (pinfunction "h2_h2") (pintype "bidirectional"))
      (node (ref "J6") (pin "h21") (pinfunction "h21_h21") (pintype "bidirectional"))
      (node (ref "J6") (pin "h24") (pinfunction "h24_h24") (pintype "bidirectional"))
      (node (ref "J6") (pin "h27") (pinfunction "h27_h27") (pintype "bidirectional"))
      (node (ref "J6") (pin "h3") (pinfunction "h3_h3") (pintype "bidirectional"))
      (node (ref "J6") (pin "h30") (pinfunction "h30_h30") (pintype "bidirectional"))
      (node (ref "J6") (pin "h33") (pinfunction "h33_h33") (pintype "bidirectional"))
      (node (ref "J6") (pin "h36") (pinfunction "h36_h36") (pintype "bidirectional"))
      (node (ref "J6") (pin "h39") (pinfunction "h39_h39") (pintype "bidirectional"))
      (node (ref "J6") (pin "h6") (pinfunction "h6_h6") (pintype "bidirectional"))
      (node (ref "J6") (pin "h9") (pinfunction "h9_h9") (pintype "bidirectional"))
      (node (ref "J6") (pin "j1") (pinfunction "j1_j1") (pintype "bidirectional"))
      (node (ref "J6") (pin "j11") (pinfunction "j11_j11") (pintype "bidirectional"))
      (node (ref "J6") (pin "j14") (pinfunction "j14_j14") (pintype "bidirectional"))
      (node (ref "J6") (pin "j17") (pinfunction "j17_j17") (pintype "bidirectional"))
      (node (ref "J6") (pin "j20") (pinfunction "j20_j20") (pintype "bidirectional"))
      (node (ref "J6") (pin "j23") (pinfunction "j23_j23") (pintype "bidirectional"))
      (node (ref "J6") (pin "j26") (pinfunction "j26_j26") (pintype "bidirectional"))
      (node (ref "J6") (pin "j29") (pinfunction "j29_j29") (pintype "bidirectional"))
      (node (ref "J6") (pin "j32") (pinfunction "j32_j32") (pintype "bidirectional"))
      (node (ref "J6") (pin "j35") (pinfunction "j35_j35") (pintype "bidirectional"))
      (node (ref "J6") (pin "j38") (pinfunction "j38_j38") (pintype "bidirectional"))
      (node (ref "J6") (pin "j4") (pinfunction "j4_j4") (pintype "bidirectional"))
      (node (ref "J6") (pin "j40") (pinfunction "j40_j40") (pintype "bidirectional"))
      (node (ref "J6") (pin "j5") (pinfunction "j5_j5") (pintype "bidirectional"))
      (node (ref "J6") (pin "j8") (pinfunction "j8_j8") (pintype "bidirectional"))
      (node (ref "J6") (pin "k12") (pinfunction "k12_k12") (pintype "bidirectional"))
      (node (ref "J6") (pin "k15") (pinfunction "k15_k15") (pintype "bidirectional"))
      (node (ref "J6") (pin "k18") (pinfunction "k18_k18") (pintype "bidirectional"))
      (node (ref "J6") (pin "k2") (pinfunction "k2_k2") (pintype "bidirectional"))
      (node (ref "J6") (pin "k21") (pinfunction "k21_k21") (pintype "bidirectional"))
      (node (ref "J6") (pin "k24") (pinfunction "k24_k24") (pintype "bidirectional"))
      (node (ref "J6") (pin "k27") (pinfunction "k27_k27") (pintype "bidirectional"))
      (node (ref "J6") (pin "k3") (pinfunction "k3_k3") (pintype "bidirectional"))
      (node (ref "J6") (pin "k30") (pinfunction "k30_k30") (pintype "bidirectional"))
      (node (ref "J6") (pin "k33") (pinfunction "k33_k33") (pintype "bidirectional"))
      (node (ref "J6") (pin "k36") (pinfunction "k36_k36") (pintype "bidirectional"))
      (node (ref "J6") (pin "k39") (pinfunction "k39_k39") (pintype "bidirectional"))
      (node (ref "J6") (pin "k6") (pinfunction "k6_k6") (pintype "bidirectional"))
      (node (ref "J6") (pin "k9") (pinfunction "k9_k9") (pintype "bidirectional"))
    )
    (net (code "183") (name "P3V3") (class "Default")
      (node (ref "J6") (pin "c39") (pinfunction "c39_c39") (pintype "bidirectional"))
      (node (ref "J6") (pin "d36") (pinfunction "d36_d36") (pintype "bidirectional"))
      (node (ref "J6") (pin "d38") (pinfunction "d38_d38") (pintype "bidirectional"))
      (node (ref "J6") (pin "d40") (pinfunction "d40_d40") (pintype "bidirectional"))
    )
    (net (code "184") (name "P3V3D") (class "Default")
      (node (ref "R132") (pin "1") (pinfunction "1_1") (pintype "passive"))
    )
    (net (code "185") (name "P12V0") (class "Default")
      (node (ref "J6") (pin "c35") (pinfunction "c35_c35") (pintype "bidirectional"))
      (node (ref "J6") (pin "c37") (pinfunction "c37_c37") (pintype "bidirectional"))
    )
    (net (code "186") (name "VADJ") (class "Default")
      (node (ref "D3") (pin "1") (pinfunction "C_1") (pintype "passive"))
      (node (ref "D4") (pin "1") (pinfunction "C_1") (pintype "passive"))
      (node (ref "D5") (pin "1") (pinfunction "C_1") (pintype "passive"))
      (node (ref "D6") (pin "1") (pinfunction "C_1") (pintype "passive"))
      (node (ref "J6") (pin "e39") (pinfunction "e39_e39") (pintype "bidirectional"))
      (node (ref "J6") (pin "f40") (pinfunction "f40_f40") (pintype "bidirectional"))
      (node (ref "J6") (pin "g39") (pinfunction "g39_g39") (pintype "bidirectional"))
      (node (ref "J6") (pin "h40") (pinfunction "h40_h40") (pintype "bidirectional"))
    )
    (net (code "187") (name "unconnected-(B2_PANEL-Pad1)") (class "Default")
      (node (ref "B2_PANEL") (pin "1") (pinfunction "1_1") (pintype "bidirectional"))
    )
    (net (code "188") (name "unconnected-(B3_PANEL-Pad1)") (class "Default")
      (node (ref "B3_PANEL") (pin "1") (pinfunction "1_1") (pintype "bidirectional"))
    )
    (net (code "189") (name "unconnected-(J6-Pada2)") (class "Default")
      (node (ref "J6") (pin "a2") (pinfunction "a2_a2") (pintype "bidirectional+no_connect"))
    )
    (net (code "190") (name "unconnected-(J6-Pada3)") (class "Default")
      (node (ref "J6") (pin "a3") (pinfunction "a3_a3") (pintype "bidirectional+no_connect"))
    )
    (net (code "191") (name "unconnected-(J6-Pada6)") (class "Default")
      (node (ref "J6") (pin "a6") (pinfunction "a6_a6") (pintype "bidirectional+no_connect"))
    )
    (net (code "192") (name "unconnected-(J6-Pada7)") (class "Default")
      (node (ref "J6") (pin "a7") (pinfunction "a7_a7") (pintype "bidirectional+no_connect"))
    )
    (net (code "193") (name "unconnected-(J6-Pada10)") (class "Default")
      (node (ref "J6") (pin "a10") (pinfunction "a10_a10") (pintype "bidirectional+no_connect"))
    )
    (net (code "194") (name "unconnected-(J6-Pada11)") (class "Default")
      (node (ref "J6") (pin "a11") (pinfunction "a11_a11") (pintype "bidirectional+no_connect"))
    )
    (net (code "195") (name "unconnected-(J6-Pada14)") (class "Default")
      (node (ref "J6") (pin "a14") (pinfunction "a14_a14") (pintype "bidirectional+no_connect"))
    )
    (net (code "196") (name "unconnected-(J6-Pada15)") (class "Default")
      (node (ref "J6") (pin "a15") (pinfunction "a15_a15") (pintype "bidirectional+no_connect"))
    )
    (net (code "197") (name "unconnected-(J6-Pada18)") (class "Default")
      (node (ref "J6") (pin "a18") (pinfunction "a18_a18") (pintype "bidirectional+no_connect"))
    )
    (net (code "198") (name "unconnected-(J6-Pada19)") (class "Default")
      (node (ref "J6") (pin "a19") (pinfunction "a19_a19") (pintype "bidirectional+no_connect"))
    )
    (net (code "199") (name "unconnected-(J6-Pada22)") (class "Default")
      (node (ref "J6") (pin "a22") (pinfunction "a22_a22") (pintype "bidirectional+no_connect"))
    )
    (net (code "200") (name "unconnected-(J6-Pada23)") (class "Default")
      (node (ref "J6") (pin "a23") (pinfunction "a23_a23") (pintype "bidirectional+no_connect"))
    )
    (net (code "201") (name "unconnected-(J6-Pada26)") (class "Default")
      (node (ref "J6") (pin "a26") (pinfunction "a26_a26") (pintype "bidirectional+no_connect"))
    )
    (net (code "202") (name "unconnected-(J6-Pada27)") (class "Default")
      (node (ref "J6") (pin "a27") (pinfunction "a27_a27") (pintype "bidirectional+no_connect"))
    )
    (net (code "203") (name "unconnected-(J6-Pada30)") (class "Default")
      (node (ref "J6") (pin "a30") (pinfunction "a30_a30") (pintype "bidirectional+no_connect"))
    )
    (net (code "204") (name "unconnected-(J6-Pada31)") (class "Default")
      (node (ref "J6") (pin "a31") (pinfunction "a31_a31") (pintype "bidirectional+no_connect"))
    )
    (net (code "205") (name "unconnected-(J6-Pada34)") (class "Default")
      (node (ref "J6") (pin "a34") (pinfunction "a34_a34") (pintype "bidirectional+no_connect"))
    )
    (net (code "206") (name "unconnected-(J6-Pada35)") (class "Default")
      (node (ref "J6") (pin "a35") (pinfunction "a35_a35") (pintype "bidirectional+no_connect"))
    )
    (net (code "207") (name "unconnected-(J6-Pada38)") (class "Default")
      (node (ref "J6") (pin "a38") (pinfunction "a38_a38") (pintype "bidirectional+no_connect"))
    )
    (net (code "208") (name "unconnected-(J6-Pada39)") (class "Default")
      (node (ref "J6") (pin "a39") (pinfunction "a39_a39") (pintype "bidirectional+no_connect"))
    )
    (net (code "209") (name "unconnected-(J6-Padb4)") (class "Default")
      (node (ref "J6") (pin "b4") (pinfunction "b4_b4") (pintype "bidirectional+no_connect"))
    )
    (net (code "210") (name "unconnected-(J6-Padb5)") (class "Default")
      (node (ref "J6") (pin "b5") (pinfunction "b5_b5") (pintype "bidirectional+no_connect"))
    )
    (net (code "211") (name "unconnected-(J6-Padb8)") (class "Default")
      (node (ref "J6") (pin "b8") (pinfunction "b8_b8") (pintype "bidirectional+no_connect"))
    )
    (net (code "212") (name "unconnected-(J6-Padb9)") (class "Default")
      (node (ref "J6") (pin "b9") (pinfunction "b9_b9") (pintype "bidirectional+no_connect"))
    )
    (net (code "213") (name "unconnected-(J6-Padb12)") (class "Default")
      (node (ref "J6") (pin "b12") (pinfunction "b12_b12") (pintype "bidirectional+no_connect"))
    )
    (net (code "214") (name "unconnected-(J6-Padb13)") (class "Default")
      (node (ref "J6") (pin "b13") (pinfunction "b13_b13") (pintype "bidirectional+no_connect"))
    )
    (net (code "215") (name "unconnected-(J6-Padb16)") (class "Default")
      (node (ref "J6") (pin "b16") (pinfunction "b16_b16") (pintype "bidirectional+no_connect"))
    )
    (net (code "216") (name "unconnected-(J6-Padb17)") (class "Default")
      (node (ref "J6") (pin "b17") (pinfunction "b17_b17") (pintype "bidirectional+no_connect"))
    )
    (net (code "217") (name "unconnected-(J6-Padb20)") (class "Default")
      (node (ref "J6") (pin "b20") (pinfunction "b20_b20") (pintype "bidirectional+no_connect"))
    )
    (net (code "218") (name "unconnected-(J6-Padb21)") (class "Default")
      (node (ref "J6") (pin "b21") (pinfunction "b21_b21") (pintype "bidirectional+no_connect"))
    )
    (net (code "219") (name "unconnected-(J6-Padb24)") (class "Default")
      (node (ref "J6") (pin "b24") (pinfunction "b24_b24") (pintype "bidirectional+no_connect"))
    )
    (net (code "220") (name "unconnected-(J6-Padb25)") (class "Default")
      (node (ref "J6") (pin "b25") (pinfunction "b25_b25") (pintype "bidirectional+no_connect"))
    )
    (net (code "221") (name "unconnected-(J6-Padb28)") (class "Default")
      (node (ref "J6") (pin "b28") (pinfunction "b28_b28") (pintype "bidirectional+no_connect"))
    )
    (net (code "222") (name "unconnected-(J6-Padb29)") (class "Default")
      (node (ref "J6") (pin "b29") (pinfunction "b29_b29") (pintype "bidirectional+no_connect"))
    )
    (net (code "223") (name "unconnected-(J6-Padb32)") (class "Default")
      (node (ref "J6") (pin "b32") (pinfunction "b32_b32") (pintype "bidirectional+no_connect"))
    )
    (net (code "224") (name "unconnected-(J6-Padb33)") (class "Default")
      (node (ref "J6") (pin "b33") (pinfunction "b33_b33") (pintype "bidirectional+no_connect"))
    )
    (net (code "225") (name "unconnected-(J6-Padb36)") (class "Default")
      (node (ref "J6") (pin "b36") (pinfunction "b36_b36") (pintype "bidirectional+no_connect"))
    )
    (net (code "226") (name "unconnected-(J6-Padb37)") (class "Default")
      (node (ref "J6") (pin "b37") (pinfunction "b37_b37") (pintype "bidirectional+no_connect"))
    )
    (net (code "227") (name "unconnected-(J6-Padb40)") (class "Default")
      (node (ref "J6") (pin "b40") (pinfunction "b40_b40") (pintype "bidirectional+no_connect"))
    )
    (net (code "228") (name "unconnected-(J6-Padc2)") (class "Default")
      (node (ref "J6") (pin "c2") (pinfunction "c2_c2") (pintype "bidirectional+no_connect"))
    )
    (net (code "229") (name "unconnected-(J6-Padc3)") (class "Default")
      (node (ref "J6") (pin "c3") (pinfunction "c3_c3") (pintype "bidirectional+no_connect"))
    )
    (net (code "230") (name "unconnected-(J6-Padc6)") (class "Default")
      (node (ref "J6") (pin "c6") (pinfunction "c6_c6") (pintype "bidirectional+no_connect"))
    )
    (net (code "231") (name "unconnected-(J6-Padc7)") (class "Default")
      (node (ref "J6") (pin "c7") (pinfunction "c7_c7") (pintype "bidirectional+no_connect"))
    )
    (net (code "232") (name "unconnected-(J6-Padd1)") (class "Default")
      (node (ref "J6") (pin "d1") (pinfunction "d1_d1") (pintype "bidirectional+no_connect"))
    )
    (net (code "233") (name "unconnected-(J6-Padd4)") (class "Default")
      (node (ref "J6") (pin "d4") (pinfunction "d4_d4") (pintype "bidirectional+no_connect"))
    )
    (net (code "234") (name "unconnected-(J6-Padd5)") (class "Default")
      (node (ref "J6") (pin "d5") (pinfunction "d5_d5") (pintype "bidirectional+no_connect"))
    )
    (net (code "235") (name "unconnected-(J6-Padd29)") (class "Default")
      (node (ref "J6") (pin "d29") (pinfunction "d29_d29") (pintype "bidirectional+no_connect"))
    )
    (net (code "236") (name "unconnected-(J6-Padd33)") (class "Default")
      (node (ref "J6") (pin "d33") (pinfunction "d33_d33") (pintype "bidirectional+no_connect"))
    )
    (net (code "237") (name "unconnected-(J6-Padd34)") (class "Default")
      (node (ref "J6") (pin "d34") (pinfunction "d34_d34") (pintype "bidirectional+no_connect"))
    )
    (net (code "238") (name "unconnected-(J6-Padk1)") (class "Default")
      (node (ref "J6") (pin "k1") (pinfunction "k1_k1") (pintype "bidirectional+no_connect"))
    )
  )
)
